# schematic.net
KiCad netlist of a schematic drawn in Altium Designer
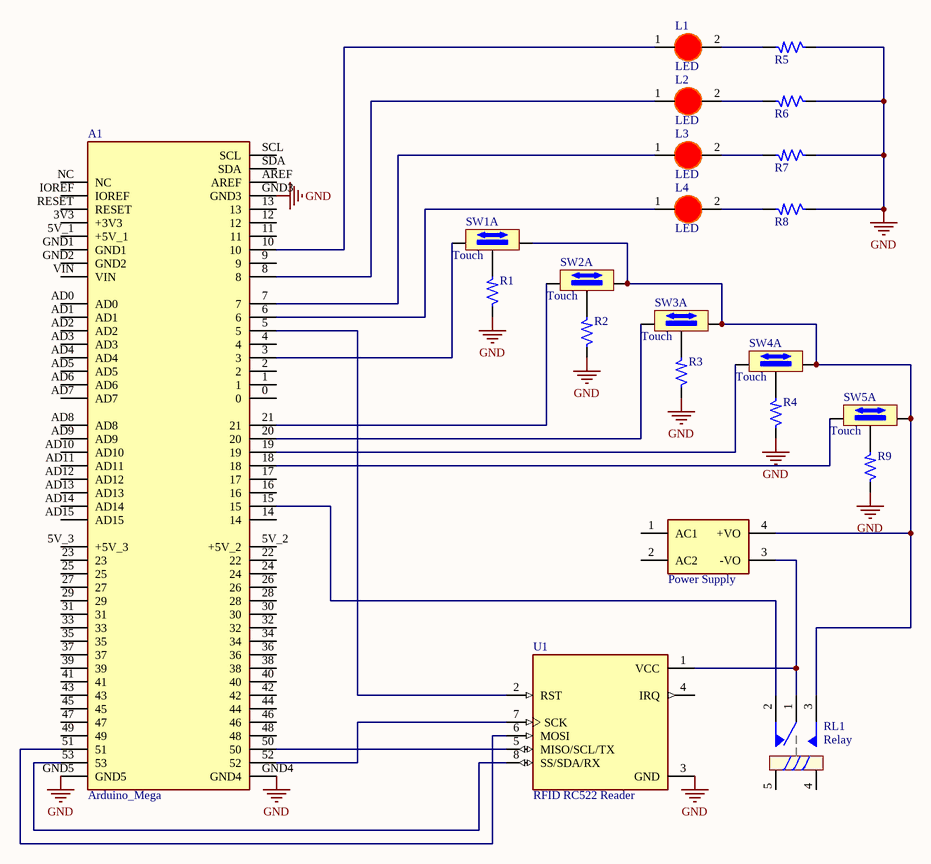
[diagram p0: schematic.schdoc]

(export (version "E")
  (design (tool "Eeschema 10.0.6"))
  (components
    (comp (ref "A1")
      (value "Arduino_Mega")
      (footprint "Arduino_Mega")
      (fields (field (name "MP") "A000067") (field (name "MF") "Arduino"))
      (libsource (lib "Arduino_Mega") (part "Arduino_Mega"))
    )
    (comp (ref "L1")
      (value "LED")
      (footprint "LED-5MM-RED")
      (description "Cắm")
      (libsource (lib "Led") (part "LED 5mm Do"))
    )
    (comp (ref "L2")
      (value "LED")
      (footprint "LED-5MM-RED")
      (description "Cắm")
      (libsource (lib "Led") (part "LED 5mm Do"))
    )
    (comp (ref "L3")
      (value "LED")
      (footprint "LED-5MM-RED")
      (description "Cắm")
      (libsource (lib "Led") (part "LED 5mm Do"))
    )
    (comp (ref "L4")
      (value "LED")
      (footprint "LED-5MM-RED")
      (description "Cắm")
      (libsource (lib "Led") (part "LED 5mm Do"))
    )
    (comp (ref "Power Supply")
      (value "Chuyen nguon 5V")
      (footprint "Module1:Nguon HI-LINK 5M05")
      (description "AC DC 220V to 5V 5W 5Watt Isolated Switching Step-Down Power Supply Module Converter")
      (fields (field (name "MF") "Hi-link") (field (name "MP") "HLK-5M05"))
      (libsource (lib "Module1") (part "Nguon Hi-Link HLK-5M05"))
    )
    (comp (ref "R1")
      (value "1k")
      (footprint "SM-1206")
      (description "Resistor 1/4W")
      (libsource (lib "syhaunguyen") (part "R"))
    )
    (comp (ref "R2")
      (value "1k")
      (footprint "SM-1206")
      (description "Resistor 1/4W")
      (libsource (lib "syhaunguyen") (part "R"))
    )
    (comp (ref "R3")
      (value "1k")
      (footprint "SM-1206")
      (description "Resistor 1/4W")
      (libsource (lib "syhaunguyen") (part "R"))
    )
    (comp (ref "R4")
      (value "1k")
      (footprint "SM-1206")
      (description "Resistor 1/4W")
      (libsource (lib "syhaunguyen") (part "R"))
    )
    (comp (ref "R5")
      (value "1k")
      (footprint "SM-1206")
      (description "Resistor 1/4W")
      (libsource (lib "syhaunguyen") (part "R"))
    )
    (comp (ref "R6")
      (value "1k")
      (footprint "SM-1206")
      (description "Resistor 1/4W")
      (libsource (lib "syhaunguyen") (part "R"))
    )
    (comp (ref "R7")
      (value "1k")
      (footprint "SM-1206")
      (description "Resistor 1/4W")
      (libsource (lib "syhaunguyen") (part "R"))
    )
    (comp (ref "R8")
      (value "1k")
      (footprint "SM-1206")
      (description "Resistor 1/4W")
      (libsource (lib "syhaunguyen") (part "R"))
    )
    (comp (ref "R9")
      (value "1k")
      (footprint "SM-1206")
      (description "Resistor 1/4W")
      (libsource (lib "syhaunguyen") (part "R"))
    )
    (comp (ref "RL1")
      (value "Relay")
      (footprint "Relay 5 Chan SRD")
      (description "Relay 5 Chan")
      (libsource (lib "Component") (part "Relay 5 Chan SRD"))
    )
    (comp (ref "SW1")
      (value "Touch")
      (footprint "SWDPDT_1.5x1")
      (description "Switch SPDT")
      (fields (field (name "CREAT BY") "VanDungEvn@Gmail.com"))
      (libsource (lib "My Library") (part "SWDPDT"))
    )
    (comp (ref "SW2")
      (value "Touch")
      (footprint "SWDPDT_1.5x1")
      (description "Switch SPDT")
      (fields (field (name "CREAT BY") "VanDungEvn@Gmail.com"))
      (libsource (lib "My Library") (part "SWDPDT"))
    )
    (comp (ref "SW3")
      (value "Touch")
      (footprint "SWDPDT_1.5x1")
      (description "Switch SPDT")
      (fields (field (name "CREAT BY") "VanDungEvn@Gmail.com"))
      (libsource (lib "My Library") (part "SWDPDT"))
    )
    (comp (ref "SW4")
      (value "Touch")
      (footprint "SWDPDT_1.5x1")
      (description "Switch SPDT")
      (fields (field (name "CREAT BY") "VanDungEvn@Gmail.com"))
      (libsource (lib "My Library") (part "SWDPDT"))
    )
    (comp (ref "SW5")
      (value "Touch")
      (footprint "SWDPDT_1.5x1")
      (description "Switch SPDT")
      (fields (field (name "CREAT BY") "VanDungEvn@Gmail.com"))
      (libsource (lib "My Library") (part "SWDPDT"))
    )
    (comp (ref "U1")
      (value "RFID RC522 Reader")
      (footprint "MODULE_CEG006900")
      (description "RFID RC522 Reader IC Card Module Tags SPI Interface Read and Write")
      (fields (field (name "MP") "CEG006900") (field (name "MF") "YKS"))
      (libsource (lib "CEG006900") (part "CEG006900"))
    )
  )
  (nets
    (net (code "1") (name "GND") (class "Default")
      (node (ref "A1") (pin "GND3") (pinfunction "GND3_GND3") (pintype "passive"))
      (node (ref "A1") (pin "GND4") (pinfunction "GND4_GND4") (pintype "passive"))
      (node (ref "A1") (pin "GND5") (pinfunction "GND5_GND5") (pintype "passive"))
      (node (ref "R1") (pin "1") (pinfunction "1_1") (pintype "passive"))
      (node (ref "R2") (pin "1") (pinfunction "1_1") (pintype "passive"))
      (node (ref "R3") (pin "1") (pinfunction "1_1") (pintype "passive"))
      (node (ref "R4") (pin "1") (pinfunction "1_1") (pintype "passive"))
      (node (ref "R5") (pin "1") (pinfunction "1_1") (pintype "passive"))
      (node (ref "R6") (pin "1") (pinfunction "1_1") (pintype "passive"))
      (node (ref "R7") (pin "1") (pinfunction "1_1") (pintype "passive"))
      (node (ref "R8") (pin "1") (pinfunction "1_1") (pintype "passive"))
      (node (ref "R9") (pin "1") (pinfunction "1_1") (pintype "passive"))
      (node (ref "U1") (pin "3") (pinfunction "GND_3") (pintype "power_in"))
    )
    (net (code "2") (name "Net-(A1-Pad3)") (class "Default")
      (node (ref "A1") (pin "3") (pinfunction "3_3") (pintype "passive"))
      (node (ref "SW1") (pin "1") (pinfunction "1_1") (pintype "passive"))
    )
    (net (code "3") (name "Net-(A1-Pad15)") (class "Default")
      (node (ref "A1") (pin "15") (pinfunction "15_15") (pintype "passive"))
      (node (ref "RL1") (pin "2") (pinfunction "2_2") (pintype "passive"))
    )
    (net (code "4") (name "Net-(A1-Pad18)") (class "Default")
      (node (ref "A1") (pin "18") (pinfunction "18_18") (pintype "passive"))
      (node (ref "SW5") (pin "1") (pinfunction "1_1") (pintype "passive"))
    )
    (net (code "5") (name "Net-(A1-Pad19)") (class "Default")
      (node (ref "A1") (pin "19") (pinfunction "19_19") (pintype "passive"))
      (node (ref "SW4") (pin "1") (pinfunction "1_1") (pintype "passive"))
    )
    (net (code "6") (name "Net-(A1-Pad20)") (class "Default")
      (node (ref "A1") (pin "20") (pinfunction "20_20") (pintype "passive"))
      (node (ref "SW3") (pin "1") (pinfunction "1_1") (pintype "passive"))
    )
    (net (code "7") (name "Net-(A1-Pad21)") (class "Default")
      (node (ref "A1") (pin "21") (pinfunction "21_21") (pintype "passive"))
      (node (ref "SW2") (pin "1") (pinfunction "1_1") (pintype "passive"))
    )
    (net (code "8") (name "Net-(L1-A)") (class "Default")
      (node (ref "A1") (pin "10") (pinfunction "10_10") (pintype "passive"))
      (node (ref "L1") (pin "1") (pinfunction "A_1") (pintype "passive"))
    )
    (net (code "9") (name "Net-(L1-K)") (class "Default")
      (node (ref "L1") (pin "2") (pinfunction "K_2") (pintype "passive"))
      (node (ref "R5") (pin "2") (pinfunction "2_2") (pintype "passive"))
    )
    (net (code "10") (name "Net-(L2-A)") (class "Default")
      (node (ref "A1") (pin "8") (pinfunction "8_8") (pintype "passive"))
      (node (ref "L2") (pin "1") (pinfunction "A_1") (pintype "passive"))
    )
    (net (code "11") (name "Net-(L2-K)") (class "Default")
      (node (ref "L2") (pin "2") (pinfunction "K_2") (pintype "passive"))
      (node (ref "R6") (pin "2") (pinfunction "2_2") (pintype "passive"))
    )
    (net (code "12") (name "Net-(L3-A)") (class "Default")
      (node (ref "A1") (pin "7") (pinfunction "7_7") (pintype "passive"))
      (node (ref "L3") (pin "1") (pinfunction "A_1") (pintype "passive"))
    )
    (net (code "13") (name "Net-(L3-K)") (class "Default")
      (node (ref "L3") (pin "2") (pinfunction "K_2") (pintype "passive"))
      (node (ref "R7") (pin "2") (pinfunction "2_2") (pintype "passive"))
    )
    (net (code "14") (name "Net-(L4-A)") (class "Default")
      (node (ref "A1") (pin "6") (pinfunction "6_6") (pintype "passive"))
      (node (ref "L4") (pin "1") (pinfunction "A_1") (pintype "passive"))
    )
    (net (code "15") (name "Net-(L4-K)") (class "Default")
      (node (ref "L4") (pin "2") (pinfunction "K_2") (pintype "passive"))
      (node (ref "R8") (pin "2") (pinfunction "2_2") (pintype "passive"))
    )
    (net (code "16") (name "Net-(Power Supply-+VO)") (class "Default")
      (node (ref "Power Supply") (pin "4") (pinfunction "+VO_4") (pintype "passive"))
      (node (ref "RL1") (pin "3") (pinfunction "3_3") (pintype "passive"))
      (node (ref "SW1") (pin "3") (pinfunction "3_3") (pintype "passive"))
      (node (ref "SW2") (pin "3") (pinfunction "3_3") (pintype "passive"))
      (node (ref "SW3") (pin "3") (pinfunction "3_3") (pintype "passive"))
      (node (ref "SW4") (pin "3") (pinfunction "3_3") (pintype "passive"))
      (node (ref "SW5") (pin "3") (pinfunction "3_3") (pintype "passive"))
    )
    (net (code "17") (name "Net-(Power Supply--VO)") (class "Default")
      (node (ref "Power Supply") (pin "3") (pinfunction "-VO_3") (pintype "passive"))
      (node (ref "RL1") (pin "1") (pinfunction "1_1") (pintype "passive"))
      (node (ref "U1") (pin "1") (pinfunction "VCC_1") (pintype "power_in"))
    )
    (net (code "18") (name "Net-(R1-Pad2)") (class "Default")
      (node (ref "R1") (pin "2") (pinfunction "2_2") (pintype "passive"))
      (node (ref "SW1") (pin "2") (pinfunction "2_2") (pintype "passive"))
    )
    (net (code "19") (name "Net-(R2-Pad2)") (class "Default")
      (node (ref "R2") (pin "2") (pinfunction "2_2") (pintype "passive"))
      (node (ref "SW2") (pin "2") (pinfunction "2_2") (pintype "passive"))
    )
    (net (code "20") (name "Net-(R3-Pad2)") (class "Default")
      (node (ref "R3") (pin "2") (pinfunction "2_2") (pintype "passive"))
      (node (ref "SW3") (pin "2") (pinfunction "2_2") (pintype "passive"))
    )
    (net (code "21") (name "Net-(R4-Pad2)") (class "Default")
      (node (ref "R4") (pin "2") (pinfunction "2_2") (pintype "passive"))
      (node (ref "SW4") (pin "2") (pinfunction "2_2") (pintype "passive"))
    )
    (net (code "22") (name "Net-(R9-Pad2)") (class "Default")
      (node (ref "R9") (pin "2") (pinfunction "2_2") (pintype "passive"))
      (node (ref "SW5") (pin "2") (pinfunction "2_2") (pintype "passive"))
    )
    (net (code "23") (name "Net-(U1-MISO{slash}SCL{slash}TX)") (class "Default")
      (node (ref "A1") (pin "50") (pinfunction "50_50") (pintype "passive"))
      (node (ref "U1") (pin "5") (pinfunction "MISO/SCL/TX_5") (pintype "bidirectional"))
    )
    (net (code "24") (name "Net-(U1-MOSI)") (class "Default")
      (node (ref "A1") (pin "51") (pinfunction "51_51") (pintype "passive"))
      (node (ref "U1") (pin "6") (pinfunction "MOSI_6") (pintype "input"))
    )
    (net (code "25") (name "Net-(U1-RST)") (class "Default")
      (node (ref "A1") (pin "5") (pinfunction "5_5") (pintype "passive"))
      (node (ref "U1") (pin "2") (pinfunction "RST_2") (pintype "input"))
    )
    (net (code "26") (name "Net-(U1-SCK)") (class "Default")
      (node (ref "A1") (pin "52") (pinfunction "52_52") (pintype "passive"))
      (node (ref "U1") (pin "7") (pinfunction "SCK_7") (pintype "input"))
    )
    (net (code "27") (name "Net-(U1-SS{slash}SDA{slash}RX)") (class "Default")
      (node (ref "A1") (pin "53") (pinfunction "53_53") (pintype "passive"))
      (node (ref "U1") (pin "8") (pinfunction "SS/SDA/RX_8") (pintype "bidirectional"))
    )
    (net (code "28") (name "unconnected-(A1-+3V3-Pad3V3)") (class "Default")
      (node (ref "A1") (pin "3V3") (pinfunction "+3V3_3V3") (pintype "passive"))
    )
    (net (code "29") (name "unconnected-(A1-+5V_1-Pad5V_1)") (class "Default")
      (node (ref "A1") (pin "5V_1") (pinfunction "+5V_1_5V_1") (pintype "passive"))
    )
    (net (code "30") (name "unconnected-(A1-+5V_2-Pad5V_2)") (class "Default")
      (node (ref "A1") (pin "5V_2") (pinfunction "+5V_2_5V_2") (pintype "passive"))
    )
    (net (code "31") (name "unconnected-(A1-+5V_3-Pad5V_3)") (class "Default")
      (node (ref "A1") (pin "5V_3") (pinfunction "+5V_3_5V_3") (pintype "passive"))
    )
    (net (code "32") (name "unconnected-(A1-Pad0)") (class "Default")
      (node (ref "A1") (pin "0") (pinfunction "0_0") (pintype "passive"))
    )
    (net (code "33") (name "unconnected-(A1-Pad1)") (class "Default")
      (node (ref "A1") (pin "1") (pinfunction "1_1") (pintype "passive"))
    )
    (net (code "34") (name "unconnected-(A1-Pad2)") (class "Default")
      (node (ref "A1") (pin "2") (pinfunction "2_2") (pintype "passive"))
    )
    (net (code "35") (name "unconnected-(A1-Pad4)") (class "Default")
      (node (ref "A1") (pin "4") (pinfunction "4_4") (pintype "passive"))
    )
    (net (code "36") (name "unconnected-(A1-Pad9)") (class "Default")
      (node (ref "A1") (pin "9") (pinfunction "9_9") (pintype "passive"))
    )
    (net (code "37") (name "unconnected-(A1-Pad11)") (class "Default")
      (node (ref "A1") (pin "11") (pinfunction "11_11") (pintype "passive"))
    )
    (net (code "38") (name "unconnected-(A1-Pad12)") (class "Default")
      (node (ref "A1") (pin "12") (pinfunction "12_12") (pintype "passive"))
    )
    (net (code "39") (name "unconnected-(A1-Pad13)") (class "Default")
      (node (ref "A1") (pin "13") (pinfunction "13_13") (pintype "passive"))
    )
    (net (code "40") (name "unconnected-(A1-Pad14)") (class "Default")
      (node (ref "A1") (pin "14") (pinfunction "14_14") (pintype "passive"))
    )
    (net (code "41") (name "unconnected-(A1-Pad16)") (class "Default")
      (node (ref "A1") (pin "16") (pinfunction "16_16") (pintype "passive"))
    )
    (net (code "42") (name "unconnected-(A1-Pad17)") (class "Default")
      (node (ref "A1") (pin "17") (pinfunction "17_17") (pintype "passive"))
    )
    (net (code "43") (name "unconnected-(A1-Pad22)") (class "Default")
      (node (ref "A1") (pin "22") (pinfunction "22_22") (pintype "passive"))
    )
    (net (code "44") (name "unconnected-(A1-Pad23)") (class "Default")
      (node (ref "A1") (pin "23") (pinfunction "23_23") (pintype "passive"))
    )
    (net (code "45") (name "unconnected-(A1-Pad24)") (class "Default")
      (node (ref "A1") (pin "24") (pinfunction "24_24") (pintype "passive"))
    )
    (net (code "46") (name "unconnected-(A1-Pad25)") (class "Default")
      (node (ref "A1") (pin "25") (pinfunction "25_25") (pintype "passive"))
    )
    (net (code "47") (name "unconnected-(A1-Pad26)") (class "Default")
      (node (ref "A1") (pin "26") (pinfunction "26_26") (pintype "passive"))
    )
    (net (code "48") (name "unconnected-(A1-Pad27)") (class "Default")
      (node (ref "A1") (pin "27") (pinfunction "27_27") (pintype "passive"))
    )
    (net (code "49") (name "unconnected-(A1-Pad28)") (class "Default")
      (node (ref "A1") (pin "28") (pinfunction "28_28") (pintype "passive"))
    )
    (net (code "50") (name "unconnected-(A1-Pad29)") (class "Default")
      (node (ref "A1") (pin "29") (pinfunction "29_29") (pintype "passive"))
    )
    (net (code "51") (name "unconnected-(A1-Pad30)") (class "Default")
      (node (ref "A1") (pin "30") (pinfunction "30_30") (pintype "passive"))
    )
    (net (code "52") (name "unconnected-(A1-Pad31)") (class "Default")
      (node (ref "A1") (pin "31") (pinfunction "31_31") (pintype "passive"))
    )
    (net (code "53") (name "unconnected-(A1-Pad32)") (class "Default")
      (node (ref "A1") (pin "32") (pinfunction "32_32") (pintype "passive"))
    )
    (net (code "54") (name "unconnected-(A1-Pad33)") (class "Default")
      (node (ref "A1") (pin "33") (pinfunction "33_33") (pintype "passive"))
    )
    (net (code "55") (name "unconnected-(A1-Pad34)") (class "Default")
      (node (ref "A1") (pin "34") (pinfunction "34_34") (pintype "passive"))
    )
    (net (code "56") (name "unconnected-(A1-Pad35)") (class "Default")
      (node (ref "A1") (pin "35") (pinfunction "35_35") (pintype "passive"))
    )
    (net (code "57") (name "unconnected-(A1-Pad36)") (class "Default")
      (node (ref "A1") (pin "36") (pinfunction "36_36") (pintype "passive"))
    )
    (net (code "58") (name "unconnected-(A1-Pad37)") (class "Default")
      (node (ref "A1") (pin "37") (pinfunction "37_37") (pintype "passive"))
    )
    (net (code "59") (name "unconnected-(A1-Pad38)") (class "Default")
      (node (ref "A1") (pin "38") (pinfunction "38_38") (pintype "passive"))
    )
    (net (code "60") (name "unconnected-(A1-Pad39)") (class "Default")
      (node (ref "A1") (pin "39") (pinfunction "39_39") (pintype "passive"))
    )
    (net (code "61") (name "unconnected-(A1-Pad40)") (class "Default")
      (node (ref "A1") (pin "40") (pinfunction "40_40") (pintype "passive"))
    )
    (net (code "62") (name "unconnected-(A1-Pad41)") (class "Default")
      (node (ref "A1") (pin "41") (pinfunction "41_41") (pintype "passive"))
    )
    (net (code "63") (name "unconnected-(A1-Pad42)") (class "Default")
      (node (ref "A1") (pin "42") (pinfunction "42_42") (pintype "passive"))
    )
    (net (code "64") (name "unconnected-(A1-Pad43)") (class "Default")
      (node (ref "A1") (pin "43") (pinfunction "43_43") (pintype "passive"))
    )
    (net (code "65") (name "unconnected-(A1-Pad44)") (class "Default")
      (node (ref "A1") (pin "44") (pinfunction "44_44") (pintype "passive"))
    )
    (net (code "66") (name "unconnected-(A1-Pad45)") (class "Default")
      (node (ref "A1") (pin "45") (pinfunction "45_45") (pintype "passive"))
    )
    (net (code "67") (name "unconnected-(A1-Pad46)") (class "Default")
      (node (ref "A1") (pin "46") (pinfunction "46_46") (pintype "passive"))
    )
    (net (code "68") (name "unconnected-(A1-Pad47)") (class "Default")
      (node (ref "A1") (pin "47") (pinfunction "47_47") (pintype "passive"))
    )
    (net (code "69") (name "unconnected-(A1-Pad48)") (class "Default")
      (node (ref "A1") (pin "48") (pinfunction "48_48") (pintype "passive"))
    )
    (net (code "70") (name "unconnected-(A1-Pad49)") (class "Default")
      (node (ref "A1") (pin "49") (pinfunction "49_49") (pintype "passive"))
    )
    (net (code "71") (name "unconnected-(A1-PadAD0)") (class "Default")
      (node (ref "A1") (pin "AD0") (pinfunction "AD0_AD0") (pintype "passive"))
    )
    (net (code "72") (name "unconnected-(A1-PadAD1)") (class "Default")
      (node (ref "A1") (pin "AD1") (pinfunction "AD1_AD1") (pintype "passive"))
    )
    (net (code "73") (name "unconnected-(A1-PadAD2)") (class "Default")
      (node (ref "A1") (pin "AD2") (pinfunction "AD2_AD2") (pintype "passive"))
    )
    (net (code "74") (name "unconnected-(A1-PadAD3)") (class "Default")
      (node (ref "A1") (pin "AD3") (pinfunction "AD3_AD3") (pintype "passive"))
    )
    (net (code "75") (name "unconnected-(A1-PadAD4)") (class "Default")
      (node (ref "A1") (pin "AD4") (pinfunction "AD4_AD4") (pintype "passive"))
    )
    (net (code "76") (name "unconnected-(A1-PadAD5)") (class "Default")
      (node (ref "A1") (pin "AD5") (pinfunction "AD5_AD5") (pintype "passive"))
    )
    (net (code "77") (name "unconnected-(A1-PadAD6)") (class "Default")
      (node (ref "A1") (pin "AD6") (pinfunction "AD6_AD6") (pintype "passive"))
    )
    (net (code "78") (name "unconnected-(A1-PadAD7)") (class "Default")
      (node (ref "A1") (pin "AD7") (pinfunction "AD7_AD7") (pintype "passive"))
    )
    (net (code "79") (name "unconnected-(A1-PadAD8)") (class "Default")
      (node (ref "A1") (pin "AD8") (pinfunction "AD8_AD8") (pintype "passive"))
    )
    (net (code "80") (name "unconnected-(A1-PadAD9)") (class "Default")
      (node (ref "A1") (pin "AD9") (pinfunction "AD9_AD9") (pintype "passive"))
    )
    (net (code "81") (name "unconnected-(A1-PadAD10)") (class "Default")
      (node (ref "A1") (pin "AD10") (pinfunction "AD10_AD10") (pintype "passive"))
    )
    (net (code "82") (name "unconnected-(A1-PadAD11)") (class "Default")
      (node (ref "A1") (pin "AD11") (pinfunction "AD11_AD11") (pintype "passive"))
    )
    (net (code "83") (name "unconnected-(A1-PadAD12)") (class "Default")
      (node (ref "A1") (pin "AD12") (pinfunction "AD12_AD12") (pintype "passive"))
    )
    (net (code "84") (name "unconnected-(A1-PadAD13)") (class "Default")
      (node (ref "A1") (pin "AD13") (pinfunction "AD13_AD13") (pintype "passive"))
    )
    (net (code "85") (name "unconnected-(A1-PadAD14)") (class "Default")
      (node (ref "A1") (pin "AD14") (pinfunction "AD14_AD14") (pintype "passive"))
    )
    (net (code "86") (name "unconnected-(A1-PadAD15)") (class "Default")
      (node (ref "A1") (pin "AD15") (pinfunction "AD15_AD15") (pintype "passive"))
    )
    (net (code "87") (name "unconnected-(A1-PadAREF)") (class "Default")
      (node (ref "A1") (pin "AREF") (pinfunction "AREF_AREF") (pintype "passive"))
    )
    (net (code "88") (name "unconnected-(A1-PadGND1)") (class "Default")
      (node (ref "A1") (pin "GND1") (pinfunction "GND1_GND1") (pintype "passive"))
    )
    (net (code "89") (name "unconnected-(A1-PadGND2)") (class "Default")
      (node (ref "A1") (pin "GND2") (pinfunction "GND2_GND2") (pintype "passive"))
    )
    (net (code "90") (name "unconnected-(A1-PadIOREF)") (class "Default")
      (node (ref "A1") (pin "IOREF") (pinfunction "IOREF_IOREF") (pintype "passive"))
    )
    (net (code "91") (name "unconnected-(A1-PadNC)") (class "Default")
      (node (ref "A1") (pin "NC") (pinfunction "NC_NC") (pintype "passive"))
    )
    (net (code "92") (name "unconnected-(A1-PadRESET)") (class "Default")
      (node (ref "A1") (pin "RESET") (pinfunction "RESET_RESET") (pintype "passive"))
    )
    (net (code "93") (name "unconnected-(A1-PadSCL)") (class "Default")
      (node (ref "A1") (pin "SCL") (pinfunction "SCL_SCL") (pintype "passive"))
    )
    (net (code "94") (name "unconnected-(A1-PadSDA)") (class "Default")
      (node (ref "A1") (pin "SDA") (pinfunction "SDA_SDA") (pintype "passive"))
    )
    (net (code "95") (name "unconnected-(A1-PadVIN)") (class "Default")
      (node (ref "A1") (pin "VIN") (pinfunction "VIN_VIN") (pintype "passive"))
    )
    (net (code "96") (name "unconnected-(Power Supply-AC1-Pad1)") (class "Default")
      (node (ref "Power Supply") (pin "1") (pinfunction "AC1_1") (pintype "passive"))
    )
    (net (code "97") (name "unconnected-(Power Supply-AC2-Pad2)") (class "Default")
      (node (ref "Power Supply") (pin "2") (pinfunction "AC2_2") (pintype "passive"))
    )
    (net (code "98") (name "unconnected-(RL1-Pad4)") (class "Default")
      (node (ref "RL1") (pin "4") (pinfunction "4_4") (pintype "passive"))
    )
    (net (code "99") (name "unconnected-(RL1-Pad5)") (class "Default")
      (node (ref "RL1") (pin "5") (pinfunction "5_5") (pintype "passive"))
    )
    (net (code "100") (name "unconnected-(U1-IRQ-Pad4)") (class "Default")
      (node (ref "U1") (pin "4") (pinfunction "IRQ_4") (pintype "output"))
    )
  )
)
